# Pixracer_V1_FMU_Alternative_1.net
KiCad netlist of a schematic drawn in Altium Designer
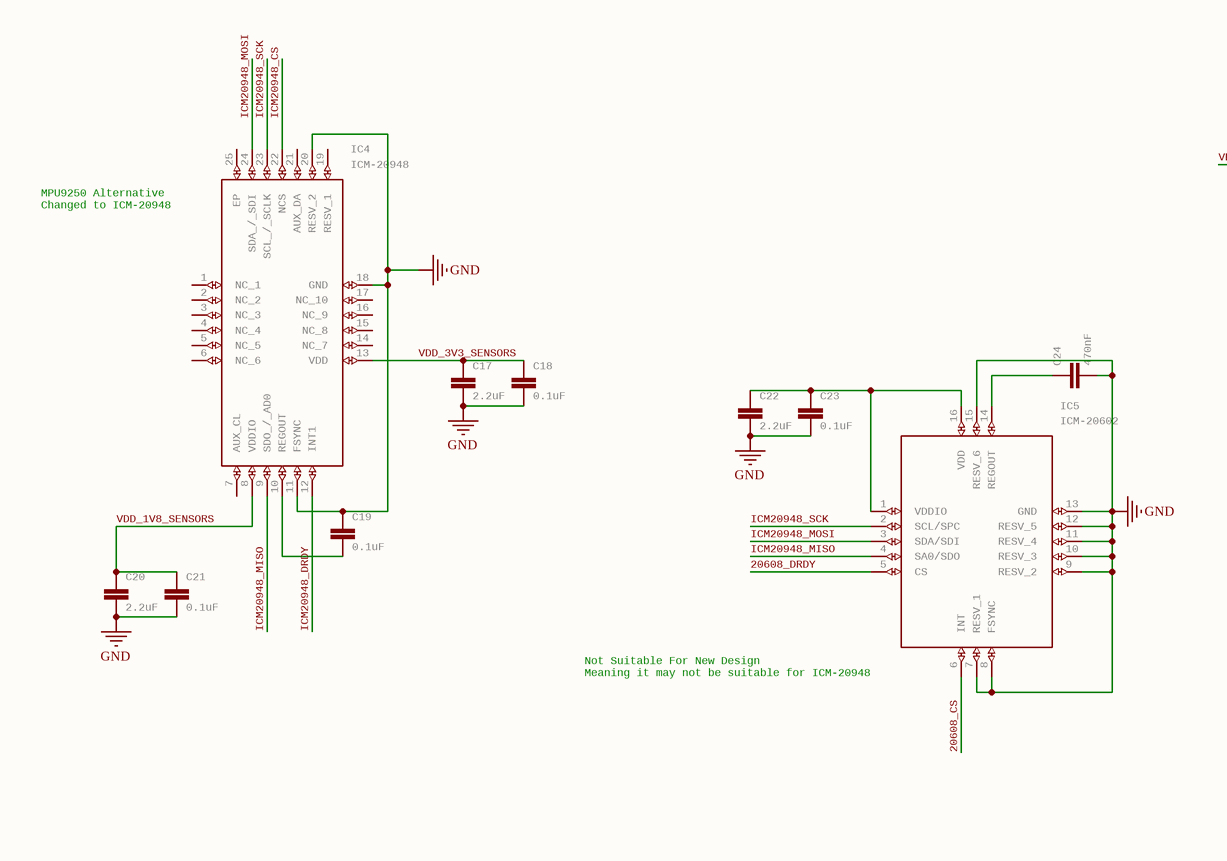
[diagram p0: Pixracer_V1_FMU_Alternative_1.SchDoc, left]
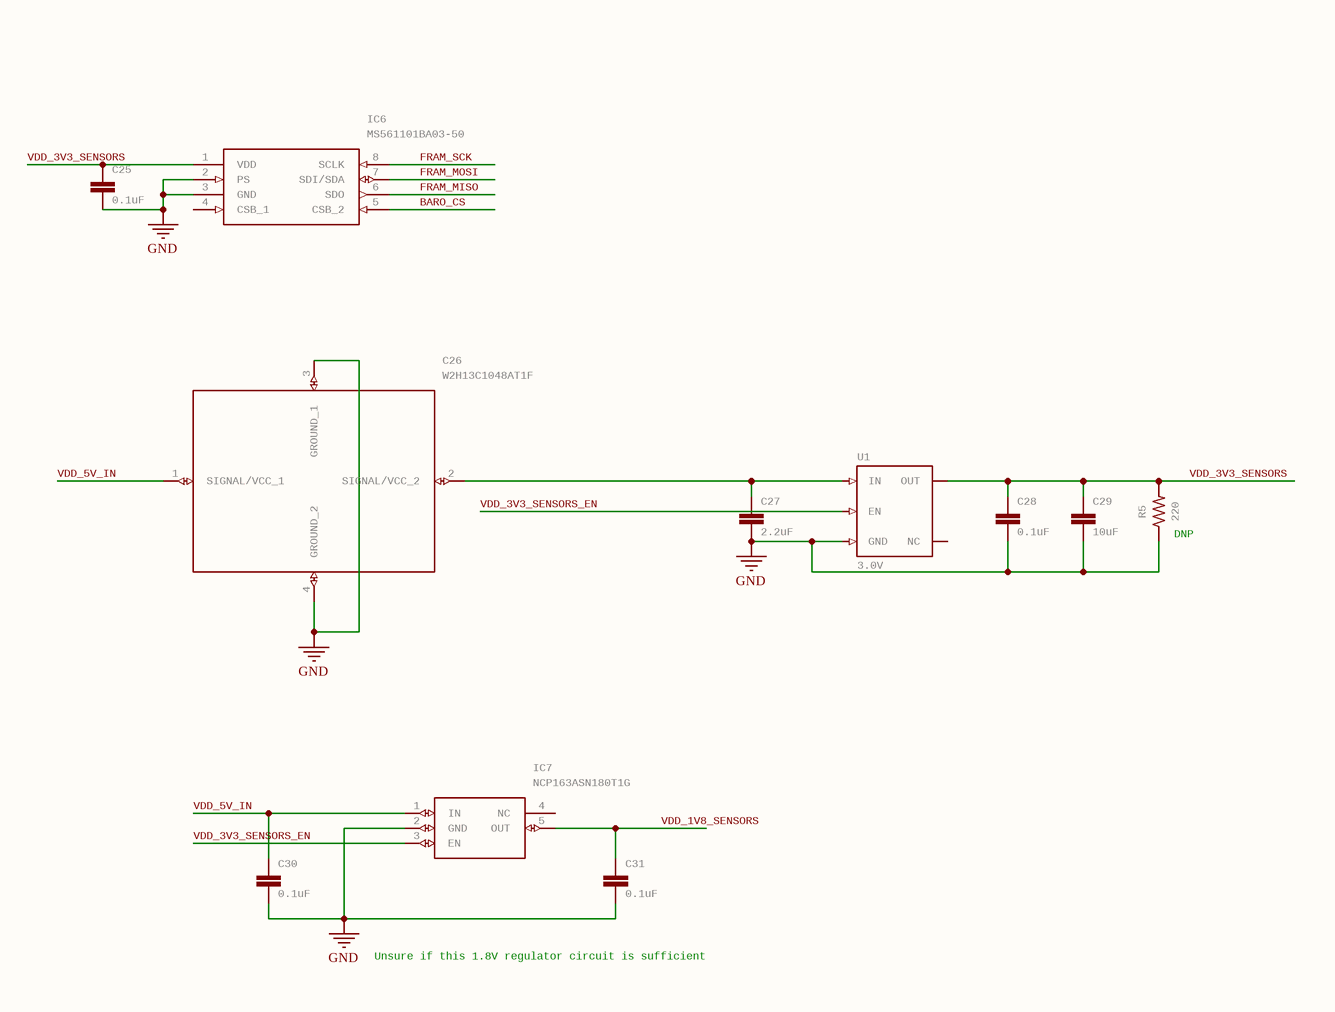
[diagram p1: Pixracer_V1_FMU_Alternative_1.SchDoc, right]

(export (version "E")
  (design (tool "Eeschema 10.0.6"))
  (components
    (comp (ref "C17")
      (value "2.2uF")
      (footprint "1206")
      (libsource (lib "SparkFun-Capacitors") (part "2.2UF-1206-50V-10%"))
    )
    (comp (ref "C18")
      (value "0.1uF")
      (footprint "0603")
      (libsource (lib "SparkFun-Capacitors") (part "0.1UF-0603-100V-10%-X7R-WE"))
    )
    (comp (ref "C19")
      (value "0.1uF")
      (footprint "0603")
      (libsource (lib "SparkFun-Capacitors") (part "0.1UF-0603-100V-10%-X7R-WE"))
    )
    (comp (ref "C20")
      (value "2.2uF")
      (footprint "1206")
      (libsource (lib "SparkFun-Capacitors") (part "2.2UF-1206-50V-10%"))
    )
    (comp (ref "C21")
      (value "0.1uF")
      (footprint "0603")
      (libsource (lib "SparkFun-Capacitors") (part "0.1UF-0603-100V-10%-X7R-WE"))
    )
    (comp (ref "C22")
      (value "2.2uF")
      (footprint "1206")
      (libsource (lib "SparkFun-Capacitors") (part "2.2UF-1206-50V-10%"))
    )
    (comp (ref "C23")
      (value "0.1uF")
      (footprint "0603")
      (libsource (lib "SparkFun-Capacitors") (part "0.1UF-0603-100V-10%-X7R-WE"))
    )
    (comp (ref "C24")
      (value "470nF")
      (footprint "0603")
      (libsource (lib "SparkFun-Capacitors") (part "470NF-0603-10V-10%-X5R"))
    )
    (comp (ref "C25")
      (value "0.1uF")
      (footprint "0603")
      (libsource (lib "SparkFun-Capacitors") (part "0.1UF-0603-100V-10%-X7R-WE"))
    )
    (comp (ref "C26")
      (value "W2H13C1048AT1F")
      (footprint "W2H13C1048AT1A")
      (description "Feed Through Capacitors 25volt 0.1uF X7R")
      (fields (field (name "MOUSER_PART_NUMBER") "581-W2H13C1048AT1F"))
      (libsource (lib "SamacSys_Parts") (part "W2H13C1048AT1F"))
    )
    (comp (ref "C27")
      (value "2.2uF")
      (footprint "1206")
      (libsource (lib "SparkFun-Capacitors") (part "2.2UF-1206-50V-10%"))
    )
    (comp (ref "C28")
      (value "0.1uF")
      (footprint "0603")
      (libsource (lib "SparkFun-Capacitors") (part "0.1UF-0603-100V-10%-X7R-WE"))
    )
    (comp (ref "C29")
      (value "10uF")
      (footprint "1206")
      (libsource (lib "SparkFun-Capacitors") (part "10UF-1206-6.3V-20%"))
    )
    (comp (ref "C30")
      (value "0.1uF")
      (footprint "0603")
      (libsource (lib "SparkFun-Capacitors") (part "0.1UF-0603-100V-10%-X7R-WE"))
    )
    (comp (ref "C31")
      (value "0.1uF")
      (footprint "0603")
      (libsource (lib "SparkFun-Capacitors") (part "0.1UF-0603-100V-10%-X7R-WE"))
    )
    (comp (ref "IC4")
      (value "ICM-20948")
      (footprint "QFN40P300X300X105-25N")
      (description "IMUs - Inertial Measurement Units World's Lowest Power 9-Axis MEMS MotionTracking Device")
      (fields (field (name "MOUSER_PART_NUMBER") "410-ICM-20948"))
      (libsource (lib "SamacSys_Parts") (part "ICM-20948"))
    )
    (comp (ref "IC5")
      (value "ICM-20602")
      (footprint "IAM20680HP")
      (fields (field (name "MOUSER_PART_NUMBER") "410-ICM-20602"))
      (libsource (lib "SamacSys_Parts") (part "ICM-20602"))
    )
    (comp (ref "IC6")
      (value "MS561101BA03-50")
      (footprint "MS561101BA03-50")
      (fields (field (name "MOUSER_PART_NUMBER") "824-MS561101BA03-50"))
      (libsource (lib "SamacSys_Parts") (part "MS561101BA03-50"))
    )
    (comp (ref "IC7")
      (value "NCP163ASN180T1G")
      (footprint "SOT95P280X145-5N")
      (description "LDO Voltage Regulators LDO Reg, Ultra-Low Noise High PSRR 1.8V")
      (fields (field (name "MOUSER_PART_NUMBER") "863-NCP163ASN180T1G"))
      (libsource (lib "SamacSys_Parts") (part "NCP163ASN180T1G"))
    )
    (comp (ref "R5")
      (value "220")
      (footprint "0603")
      (libsource (lib "SparkFun-Resistors") (part "220OHM-0603-1/10W-1%"))
    )
    (comp (ref "U1")
      (value "3.0V")
      (footprint "SOT23-5")
      (fields
        (field (name "DIGIKEY_PART") "296-40357-1-ND")
        (field (name "MANU_PART") "LP5907MFX-3.0/NOPB")
        (field (name "MOUSER_PART") "595-LP5907MFX-3.0NPB")
      )
      (libsource (lib "SparkFun-IC-Power") (part "V_REG_LP5907SOT23-3.0V"))
    )
  )
  (nets
    (net (code "1") (name "/20608_CS") (class "Default")
      (node (ref "IC5") (pin "6") (pinfunction "INT_6") (pintype "bidirectional"))
    )
    (net (code "2") (name "/20608_DRDY") (class "Default")
      (node (ref "IC5") (pin "5") (pinfunction "CS_5") (pintype "bidirectional"))
    )
    (net (code "3") (name "/BARO_CS") (class "Default")
      (node (ref "IC6") (pin "5") (pinfunction "CSB_2_5") (pintype "input"))
    )
    (net (code "4") (name "/FRAM_MISO") (class "Default")
      (node (ref "IC6") (pin "6") (pinfunction "SDO_6") (pintype "output"))
    )
    (net (code "5") (name "/FRAM_MOSI") (class "Default")
      (node (ref "IC6") (pin "7") (pinfunction "SDI/SDA_7") (pintype "bidirectional"))
    )
    (net (code "6") (name "/FRAM_SCK") (class "Default")
      (node (ref "IC6") (pin "8") (pinfunction "SCLK_8") (pintype "input"))
    )
    (net (code "7") (name "/ICM20948_CS") (class "Default")
      (node (ref "IC4") (pin "22") (pinfunction "NCS_22") (pintype "bidirectional"))
    )
    (net (code "8") (name "/ICM20948_DRDY") (class "Default")
      (node (ref "IC4") (pin "12") (pinfunction "INT1_12") (pintype "bidirectional"))
    )
    (net (code "9") (name "/ICM20948_MISO") (class "Default")
      (node (ref "IC4") (pin "9") (pinfunction "SDO_/_AD0_9") (pintype "bidirectional"))
      (node (ref "IC5") (pin "4") (pinfunction "SA0/SDO_4") (pintype "bidirectional"))
    )
    (net (code "10") (name "/ICM20948_MOSI") (class "Default")
      (node (ref "IC4") (pin "24") (pinfunction "SDA_/_SDI_24") (pintype "bidirectional"))
      (node (ref "IC5") (pin "3") (pinfunction "SDA/SDI_3") (pintype "bidirectional"))
    )
    (net (code "11") (name "/ICM20948_SCK") (class "Default")
      (node (ref "IC4") (pin "23") (pinfunction "SCL_/_SCLK_23") (pintype "bidirectional"))
      (node (ref "IC5") (pin "2") (pinfunction "SCL/SPC_2") (pintype "bidirectional"))
    )
    (net (code "12") (name "/VDD_1V8_SENSORS") (class "Default")
      (node (ref "C20") (pin "1") (pinfunction "1_1") (pintype "passive"))
      (node (ref "C21") (pin "1") (pinfunction "1_1") (pintype "passive"))
      (node (ref "C31") (pin "1") (pinfunction "1_1") (pintype "passive"))
      (node (ref "IC4") (pin "8") (pinfunction "VDDIO_8") (pintype "bidirectional"))
      (node (ref "IC7") (pin "5") (pinfunction "OUT_5") (pintype "bidirectional"))
    )
    (net (code "13") (name "/VDD_3V3_SENSORS") (class "Default")
      (node (ref "C17") (pin "1") (pinfunction "1_1") (pintype "passive"))
      (node (ref "C18") (pin "1") (pinfunction "1_1") (pintype "passive"))
      (node (ref "C25") (pin "1") (pinfunction "1_1") (pintype "passive"))
      (node (ref "C28") (pin "1") (pinfunction "1_1") (pintype "passive"))
      (node (ref "C29") (pin "1") (pinfunction "1_1") (pintype "passive"))
      (node (ref "IC4") (pin "13") (pinfunction "VDD_13") (pintype "bidirectional"))
      (node (ref "IC6") (pin "1") (pinfunction "VDD_1") (pintype "power_in"))
      (node (ref "R5") (pin "2") (pinfunction "2_2") (pintype "passive"))
      (node (ref "U1") (pin "5") (pinfunction "OUT_5") (pintype "passive"))
    )
    (net (code "14") (name "/VDD_3V3_SENSORS_EN") (class "Default")
      (node (ref "IC7") (pin "3") (pinfunction "EN_3") (pintype "bidirectional"))
      (node (ref "U1") (pin "3") (pinfunction "EN_3") (pintype "input"))
    )
    (net (code "15") (name "/VDD_5V_IN") (class "Default")
      (node (ref "C26") (pin "1") (pinfunction "SIGNAL/VCC_1_1") (pintype "bidirectional"))
      (node (ref "C30") (pin "1") (pinfunction "1_1") (pintype "passive"))
      (node (ref "IC7") (pin "1") (pinfunction "IN_1") (pintype "bidirectional"))
    )
    (net (code "16") (name "GND") (class "Default")
      (node (ref "C17") (pin "2") (pinfunction "2_2") (pintype "passive"))
      (node (ref "C18") (pin "2") (pinfunction "2_2") (pintype "passive"))
      (node (ref "C19") (pin "1") (pinfunction "1_1") (pintype "passive"))
      (node (ref "C20") (pin "2") (pinfunction "2_2") (pintype "passive"))
      (node (ref "C21") (pin "2") (pinfunction "2_2") (pintype "passive"))
      (node (ref "C22") (pin "2") (pinfunction "2_2") (pintype "passive"))
      (node (ref "C23") (pin "2") (pinfunction "2_2") (pintype "passive"))
      (node (ref "C24") (pin "2") (pinfunction "2_2") (pintype "passive"))
      (node (ref "C25") (pin "2") (pinfunction "2_2") (pintype "passive"))
      (node (ref "C26") (pin "3") (pinfunction "GROUND_1_3") (pintype "bidirectional"))
      (node (ref "C26") (pin "4") (pinfunction "GROUND_2_4") (pintype "bidirectional"))
      (node (ref "C27") (pin "2") (pinfunction "2_2") (pintype "passive"))
      (node (ref "C28") (pin "2") (pinfunction "2_2") (pintype "passive"))
      (node (ref "C29") (pin "2") (pinfunction "2_2") (pintype "passive"))
      (node (ref "C30") (pin "2") (pinfunction "2_2") (pintype "passive"))
      (node (ref "C31") (pin "2") (pinfunction "2_2") (pintype "passive"))
      (node (ref "IC4") (pin "11") (pinfunction "FSYNC_11") (pintype "bidirectional"))
      (node (ref "IC4") (pin "18") (pinfunction "GND_18") (pintype "bidirectional"))
      (node (ref "IC4") (pin "20") (pinfunction "RESV_2_20") (pintype "bidirectional"))
      (node (ref "IC5") (pin "10") (pinfunction "RESV_3_10") (pintype "bidirectional"))
      (node (ref "IC5") (pin "11") (pinfunction "RESV_4_11") (pintype "bidirectional"))
      (node (ref "IC5") (pin "12") (pinfunction "RESV_5_12") (pintype "bidirectional"))
      (node (ref "IC5") (pin "13") (pinfunction "GND_13") (pintype "bidirectional"))
      (node (ref "IC5") (pin "15") (pinfunction "RESV_6_15") (pintype "bidirectional"))
      (node (ref "IC5") (pin "7") (pinfunction "RESV_1_7") (pintype "bidirectional"))
      (node (ref "IC5") (pin "8") (pinfunction "FSYNC_8") (pintype "bidirectional"))
      (node (ref "IC5") (pin "9") (pinfunction "RESV_2_9") (pintype "bidirectional"))
      (node (ref "IC6") (pin "2") (pinfunction "PS_2") (pintype "input"))
      (node (ref "IC6") (pin "3") (pinfunction "GND_3") (pintype "power_in"))
      (node (ref "IC7") (pin "2") (pinfunction "GND_2") (pintype "bidirectional"))
      (node (ref "R5") (pin "1") (pinfunction "1_1") (pintype "passive"))
      (node (ref "U1") (pin "2") (pinfunction "GND_2") (pintype "input"))
    )
    (net (code "17") (name "Net-(C26-SIGNAL{slash}VCC_2)") (class "Default")
      (node (ref "C26") (pin "2") (pinfunction "SIGNAL/VCC_2_2") (pintype "bidirectional"))
      (node (ref "C27") (pin "1") (pinfunction "1_1") (pintype "passive"))
      (node (ref "U1") (pin "1") (pinfunction "IN_1") (pintype "input"))
    )
    (net (code "18") (name "Net-(IC4-REGOUT)") (class "Default")
      (node (ref "C19") (pin "2") (pinfunction "2_2") (pintype "passive"))
      (node (ref "IC4") (pin "10") (pinfunction "REGOUT_10") (pintype "bidirectional"))
    )
    (net (code "19") (name "Net-(IC5-REGOUT)") (class "Default")
      (node (ref "C24") (pin "1") (pinfunction "1_1") (pintype "passive"))
      (node (ref "IC5") (pin "14") (pinfunction "REGOUT_14") (pintype "bidirectional"))
    )
    (net (code "20") (name "Net-(IC5-VDD)") (class "Default")
      (node (ref "C22") (pin "1") (pinfunction "1_1") (pintype "passive"))
      (node (ref "C23") (pin "1") (pinfunction "1_1") (pintype "passive"))
      (node (ref "IC5") (pin "1") (pinfunction "VDDIO_1") (pintype "bidirectional"))
      (node (ref "IC5") (pin "16") (pinfunction "VDD_16") (pintype "bidirectional"))
    )
    (net (code "21") (name "unconnected-(IC4-AUX_CL-Pad7)") (class "Default")
      (node (ref "IC4") (pin "7") (pinfunction "AUX_CL_7") (pintype "bidirectional"))
    )
    (net (code "22") (name "unconnected-(IC4-AUX_DA-Pad21)") (class "Default")
      (node (ref "IC4") (pin "21") (pinfunction "AUX_DA_21") (pintype "bidirectional"))
    )
    (net (code "23") (name "unconnected-(IC4-EP-Pad25)") (class "Default")
      (node (ref "IC4") (pin "25") (pinfunction "EP_25") (pintype "bidirectional"))
    )
    (net (code "24") (name "unconnected-(IC4-NC_1-Pad1)") (class "Default")
      (node (ref "IC4") (pin "1") (pinfunction "NC_1_1") (pintype "bidirectional"))
    )
    (net (code "25") (name "unconnected-(IC4-NC_2-Pad2)") (class "Default")
      (node (ref "IC4") (pin "2") (pinfunction "NC_2_2") (pintype "bidirectional"))
    )
    (net (code "26") (name "unconnected-(IC4-NC_3-Pad3)") (class "Default")
      (node (ref "IC4") (pin "3") (pinfunction "NC_3_3") (pintype "bidirectional"))
    )
    (net (code "27") (name "unconnected-(IC4-NC_4-Pad4)") (class "Default")
      (node (ref "IC4") (pin "4") (pinfunction "NC_4_4") (pintype "bidirectional"))
    )
    (net (code "28") (name "unconnected-(IC4-NC_5-Pad5)") (class "Default")
      (node (ref "IC4") (pin "5") (pinfunction "NC_5_5") (pintype "bidirectional"))
    )
    (net (code "29") (name "unconnected-(IC4-NC_6-Pad6)") (class "Default")
      (node (ref "IC4") (pin "6") (pinfunction "NC_6_6") (pintype "bidirectional"))
    )
    (net (code "30") (name "unconnected-(IC4-NC_7-Pad14)") (class "Default")
      (node (ref "IC4") (pin "14") (pinfunction "NC_7_14") (pintype "bidirectional"))
    )
    (net (code "31") (name "unconnected-(IC4-NC_8-Pad15)") (class "Default")
      (node (ref "IC4") (pin "15") (pinfunction "NC_8_15") (pintype "bidirectional"))
    )
    (net (code "32") (name "unconnected-(IC4-NC_9-Pad16)") (class "Default")
      (node (ref "IC4") (pin "16") (pinfunction "NC_9_16") (pintype "bidirectional"))
    )
    (net (code "33") (name "unconnected-(IC4-NC_10-Pad17)") (class "Default")
      (node (ref "IC4") (pin "17") (pinfunction "NC_10_17") (pintype "bidirectional"))
    )
    (net (code "34") (name "unconnected-(IC4-RESV_1-Pad19)") (class "Default")
      (node (ref "IC4") (pin "19") (pinfunction "RESV_1_19") (pintype "bidirectional"))
    )
    (net (code "35") (name "unconnected-(IC6-CSB_1-Pad4)") (class "Default")
      (node (ref "IC6") (pin "4") (pinfunction "CSB_1_4") (pintype "input"))
    )
    (net (code "36") (name "unconnected-(IC7-NC-Pad4)") (class "Default")
      (node (ref "IC7") (pin "4") (pinfunction "NC_4") (pintype "passive"))
    )
    (net (code "37") (name "unconnected-(U1-NC-Pad4)") (class "Default")
      (node (ref "U1") (pin "4") (pinfunction "NC_4") (pintype "passive"))
    )
  )
)
